# Sensors.net
KiCad netlist of a schematic drawn in Altium Designer
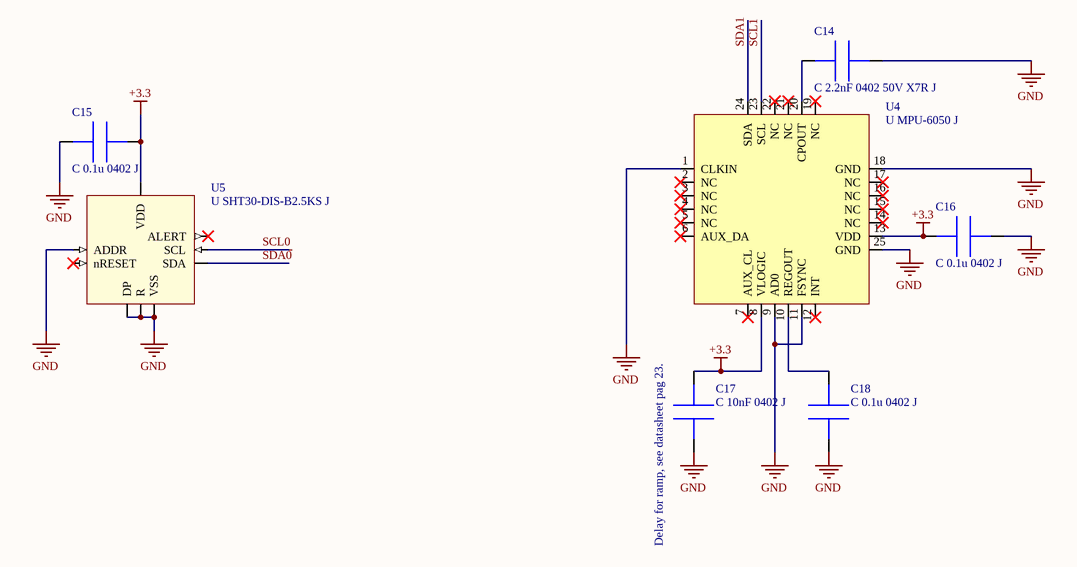
[diagram p0: Sensors.SchDoc]

(export (version "E")
  (design (tool "Eeschema 10.0.6"))
  (components
    (comp (ref "C14")
      (value "C 2.2nF 0402 50V X7R J")
      (footprint "C0402")
      (description "Cap Ceramic 0.0022uF 50V X7R 10% Pad SMD 0402 125C Automotive T/R AC0402KRX7R9BB222")
      (fields
        (field (name "MANUFACTURER") "Yageo")
        (field (name "MANUFACTURER PART NUMBER") "AC0402KRX7R9BB222")
      )
      (libsource (lib "Schlib1") (part "C 2.2nF 0402 50V X7R J"))
    )
    (comp (ref "C15")
      (value "C 0.1u 0402 J")
      (footprint "C0402")
      (description "Cap Ceramic 0.1uF 50V X7R 10% Pad SMD 0402 125C Low ESR Automotive CL05B104KB54PNC")
      (fields
        (field (name "MANUFACTURER") "Samsung")
        (field (name "MANUFACTURER PART NUMBER") "CL05B104KB54PNC")
      )
      (libsource (lib "Schlib1") (part "C 0.1u 0402 J"))
    )
    (comp (ref "C16")
      (value "C 0.1u 0402 J")
      (footprint "C0402")
      (description "Cap Ceramic 0.1uF 50V X7R 10% Pad SMD 0402 125C Low ESR Automotive CL05B104KB54PNC")
      (fields
        (field (name "MANUFACTURER") "Samsung")
        (field (name "MANUFACTURER PART NUMBER") "CL05B104KB54PNC")
      )
      (libsource (lib "Schlib1") (part "C 0.1u 0402 J"))
    )
    (comp (ref "C17")
      (value "C 10nF 0402 J")
      (footprint "C0402")
      (description "Ceramic capacitor SMD-0402 10nF /50V X7R# K +-10%, Samsung, RoHS CL05B103KB5NNNC")
      (fields
        (field (name "MANUFACTURER") "Samsung")
        (field (name "MANUFACTURER PART NUMBER") "CL05B103KB5NNNC")
      )
      (libsource (lib "Schlib1") (part "C 10nF 0402 J"))
    )
    (comp (ref "C18")
      (value "C 0.1u 0402 J")
      (footprint "C0402")
      (description "Cap Ceramic 0.1uF 50V X7R 10% Pad SMD 0402 125C Low ESR Automotive CL05B104KB54PNC")
      (fields
        (field (name "MANUFACTURER") "Samsung")
        (field (name "MANUFACTURER PART NUMBER") "CL05B104KB54PNC")
      )
      (libsource (lib "Schlib1") (part "C 0.1u 0402 J"))
    )
    (comp (ref "U4")
      (value "U MPU-6050 J")
      (footprint "MPU-6050")
      (description "IMU ACCEL/GYRO 3-AXIS I2C 24QFN")
      (fields
        (field (name "MANUFACTURER") "TDK InvenSense")
        (field (name "MANUFACTURER PART NUMBER") "MPU-6050")
      )
      (libsource (lib "Schlib1") (part "U MPU-6050 J"))
    )
    (comp (ref "U5")
      (value "U SHT30-DIS-B2.5KS J")
      (footprint "SHT30")
      (description "Humidity/Temperature Sensor Digital Serial (I2C) 8-Pin DFN EP T/R SHT30-DIS-B2.5KS")
      (fields
        (field (name "MANUFACTURER") "Sensirion")
        (field (name "MANUFACTURER PART NUMBER") "SHT30-DIS-B2.5KS")
      )
      (libsource (lib "Schlib1") (part "U SHT30-DIS-B2.5KS J"))
    )
  )
  (nets
    (net (code "1") (name "+3.3") (class "Default")
      (node (ref "C15") (pin "2") (pinfunction "2_2") (pintype "passive"))
      (node (ref "C16") (pin "1") (pinfunction "1_1") (pintype "passive"))
      (node (ref "C17") (pin "2") (pinfunction "2_2") (pintype "passive"))
      (node (ref "U4") (pin "13") (pinfunction "VDD_13") (pintype "passive"))
      (node (ref "U4") (pin "8") (pinfunction "VLOGIC_8") (pintype "passive"))
      (node (ref "U5") (pin "5") (pinfunction "VDD_5") (pintype "power_in"))
    )
    (net (code "2") (name "/SCL0") (class "Default")
      (node (ref "U5") (pin "4") (pinfunction "SCL_4") (pintype "input"))
    )
    (net (code "3") (name "/SCL1") (class "Default")
      (node (ref "U4") (pin "23") (pinfunction "SCL_23") (pintype "passive"))
    )
    (net (code "4") (name "/SDA1") (class "Default")
      (node (ref "U4") (pin "24") (pinfunction "SDA_24") (pintype "passive"))
    )
    (net (code "5") (name "/SDA~{0}") (class "Default")
      (node (ref "U5") (pin "1") (pinfunction "SDA_1") (pintype "bidirectional"))
    )
    (net (code "6") (name "GND") (class "Default")
      (node (ref "C14") (pin "2") (pinfunction "2_2") (pintype "passive"))
      (node (ref "C15") (pin "1") (pinfunction "1_1") (pintype "passive"))
      (node (ref "C16") (pin "2") (pinfunction "2_2") (pintype "passive"))
      (node (ref "C17") (pin "1") (pinfunction "1_1") (pintype "passive"))
      (node (ref "C18") (pin "1") (pinfunction "1_1") (pintype "passive"))
      (node (ref "U4") (pin "1") (pinfunction "CLKIN_1") (pintype "passive"))
      (node (ref "U4") (pin "11") (pinfunction "FSYNC_11") (pintype "passive"))
      (node (ref "U4") (pin "18") (pinfunction "GND_18") (pintype "passive"))
      (node (ref "U4") (pin "25") (pinfunction "GND_25") (pintype "passive"))
      (node (ref "U4") (pin "9") (pinfunction "AD0_9") (pintype "passive"))
      (node (ref "U5") (pin "2") (pinfunction "ADDR_2") (pintype "input"))
      (node (ref "U5") (pin "7") (pinfunction "R_7") (pintype "passive"))
      (node (ref "U5") (pin "8") (pinfunction "VSS_8") (pintype "power_in"))
      (node (ref "U5") (pin "DP") (pinfunction "DP_DP") (pintype "power_in"))
    )
    (net (code "7") (name "Net-(U4-CPOUT)") (class "Default")
      (node (ref "C14") (pin "1") (pinfunction "1_1") (pintype "passive"))
      (node (ref "U4") (pin "20") (pinfunction "CPOUT_20") (pintype "passive"))
    )
    (net (code "8") (name "Net-(U4-REGOUT)") (class "Default")
      (node (ref "C18") (pin "2") (pinfunction "2_2") (pintype "passive"))
      (node (ref "U4") (pin "10") (pinfunction "REGOUT_10") (pintype "passive"))
    )
    (net (code "9") (name "unconnected-(U4-AUX_CL-Pad7)") (class "Default")
      (node (ref "U4") (pin "7") (pinfunction "AUX_CL_7") (pintype "passive+no_connect"))
    )
    (net (code "10") (name "unconnected-(U4-AUX_DA-Pad6)") (class "Default")
      (node (ref "U4") (pin "6") (pinfunction "AUX_DA_6") (pintype "passive+no_connect"))
    )
    (net (code "11") (name "unconnected-(U4-INT-Pad12)") (class "Default")
      (node (ref "U4") (pin "12") (pinfunction "INT_12") (pintype "passive+no_connect"))
    )
    (net (code "12") (name "unconnected-(U4-NC-Pad2)") (class "Default")
      (node (ref "U4") (pin "2") (pinfunction "NC_2") (pintype "passive+no_connect"))
    )
    (net (code "13") (name "unconnected-(U4-NC-Pad3)") (class "Default")
      (node (ref "U4") (pin "3") (pinfunction "NC_3") (pintype "passive+no_connect"))
    )
    (net (code "14") (name "unconnected-(U4-NC-Pad4)") (class "Default")
      (node (ref "U4") (pin "4") (pinfunction "NC_4") (pintype "passive+no_connect"))
    )
    (net (code "15") (name "unconnected-(U4-NC-Pad5)") (class "Default")
      (node (ref "U4") (pin "5") (pinfunction "NC_5") (pintype "passive+no_connect"))
    )
    (net (code "16") (name "unconnected-(U4-NC-Pad14)") (class "Default")
      (node (ref "U4") (pin "14") (pinfunction "NC_14") (pintype "passive+no_connect"))
    )
    (net (code "17") (name "unconnected-(U4-NC-Pad15)") (class "Default")
      (node (ref "U4") (pin "15") (pinfunction "NC_15") (pintype "passive+no_connect"))
    )
    (net (code "18") (name "unconnected-(U4-NC-Pad16)") (class "Default")
      (node (ref "U4") (pin "16") (pinfunction "NC_16") (pintype "passive+no_connect"))
    )
    (net (code "19") (name "unconnected-(U4-NC-Pad17)") (class "Default")
      (node (ref "U4") (pin "17") (pinfunction "NC_17") (pintype "passive+no_connect"))
    )
    (net (code "20") (name "unconnected-(U4-NC-Pad19)") (class "Default")
      (node (ref "U4") (pin "19") (pinfunction "NC_19") (pintype "passive+no_connect"))
    )
    (net (code "21") (name "unconnected-(U4-NC-Pad21)") (class "Default")
      (node (ref "U4") (pin "21") (pinfunction "NC_21") (pintype "passive+no_connect"))
    )
    (net (code "22") (name "unconnected-(U4-NC-Pad22)") (class "Default")
      (node (ref "U4") (pin "22") (pinfunction "NC_22") (pintype "passive+no_connect"))
    )
    (net (code "23") (name "unconnected-(U5-ALERT-Pad3)") (class "Default")
      (node (ref "U5") (pin "3") (pinfunction "ALERT_3") (pintype "output+no_connect"))
    )
    (net (code "24") (name "unconnected-(U5-nRESET-Pad6)") (class "Default")
      (node (ref "U5") (pin "6") (pinfunction "nRESET_6") (pintype "input+no_connect"))
    )
  )
)
